# PiezoAmpHVDC.net
KiCad netlist of a schematic drawn in EAGLE
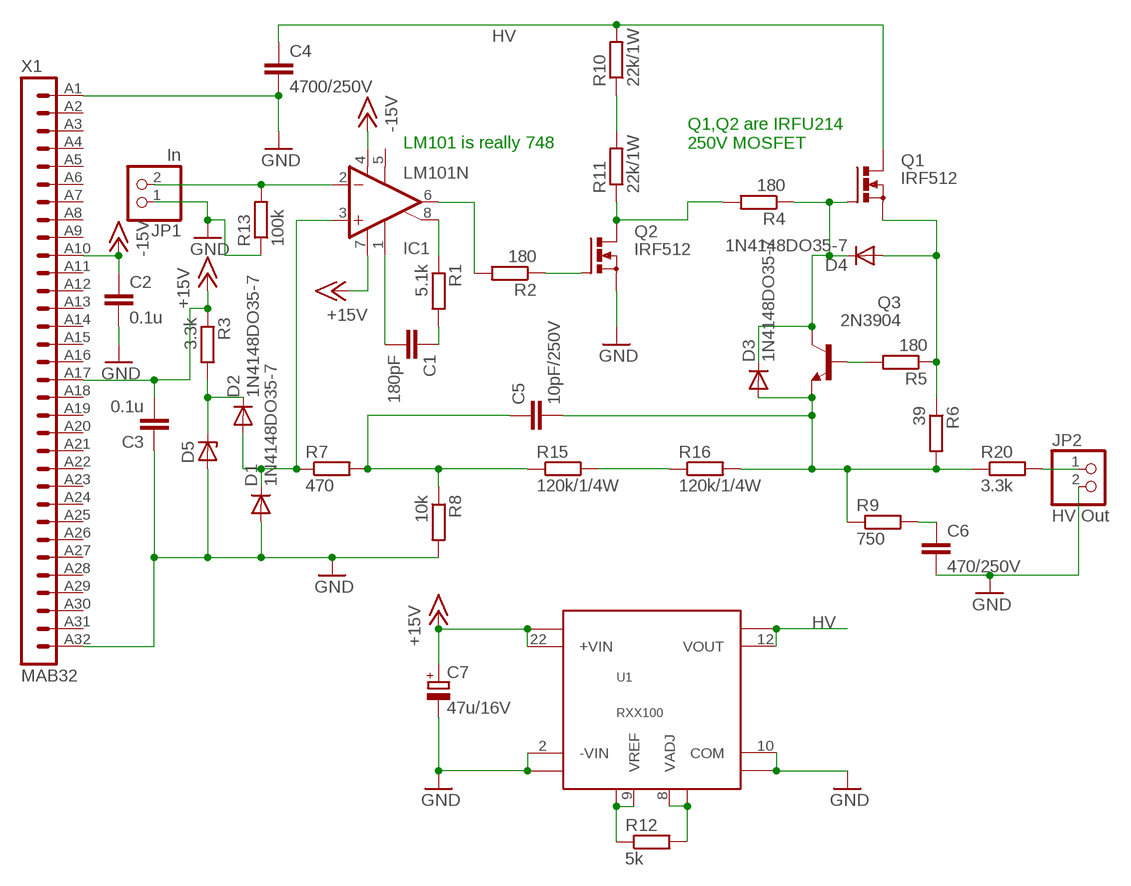
[diagram p0: schematic, sheet 1]

(export (version "E")
  (design (tool "Eeschema 10.0.6"))
  (components
    (comp (ref "C1")
      (value "180pF")
      (footprint "eagle-import:C050-030X075")
      (libsource (lib "eagle-import") (part "C-EU050-030X075"))
    )
    (comp (ref "C2")
      (value "0.1u")
      (footprint "eagle-import:C050-030X075")
      (libsource (lib "eagle-import") (part "C-EU050-030X075"))
    )
    (comp (ref "C3")
      (value "0.1u")
      (footprint "eagle-import:C050-030X075")
      (libsource (lib "eagle-import") (part "C-EU050-030X075"))
    )
    (comp (ref "C4")
      (value "4700/250V")
      (footprint "eagle-import:C075-032X103")
      (libsource (lib "eagle-import") (part "C-EU075-032X103"))
    )
    (comp (ref "C5")
      (value "10pF/250V")
      (footprint "eagle-import:C075-032X103")
      (libsource (lib "eagle-import") (part "C-EU075-032X103"))
    )
    (comp (ref "C6")
      (value "470/250V")
      (footprint "eagle-import:C075-032X103")
      (libsource (lib "eagle-import") (part "C-EU075-032X103"))
    )
    (comp (ref "C7")
      (value "47u/16V")
      (footprint "eagle-import:SANYO-OSCON_F8")
      (libsource (lib "eagle-import") (part "CPOL-EUSANYO_F8"))
    )
    (comp (ref "D1")
      (value "1N4148DO35-7")
      (footprint "eagle-import:DO35-7")
      (libsource (lib "eagle-import") (part "1N4148DO35-7"))
    )
    (comp (ref "D2")
      (value "1N4148DO35-7")
      (footprint "eagle-import:DO35-7")
      (libsource (lib "eagle-import") (part "1N4148DO35-7"))
    )
    (comp (ref "D3")
      (value "1N4148DO35-7")
      (footprint "eagle-import:DO35-7")
      (libsource (lib "eagle-import") (part "1N4148DO35-7"))
    )
    (comp (ref "D4")
      (value "1N4148DO35-7")
      (footprint "eagle-import:DO35-7")
      (libsource (lib "eagle-import") (part "1N4148DO35-7"))
    )
    (comp (ref "D5")
      (value "ZENER-DIODEDO34-7")
      (footprint "eagle-import:DO34Z7")
      (libsource (lib "eagle-import") (part "ZENER-DIODEDO34-7"))
    )
    (comp (ref "IC1")
      (value "LM101N")
      (footprint "eagle-import:DIL08")
      (libsource (lib "eagle-import") (part "LM101N"))
    )
    (comp (ref "JP1")
      (value "In")
      (footprint "eagle-import:1X02")
      (libsource (lib "eagle-import") (part "PINHD-1X2"))
    )
    (comp (ref "JP2")
      (value "HV Out")
      (footprint "eagle-import:1X02")
      (libsource (lib "eagle-import") (part "PINHD-1X2"))
    )
    (comp (ref "Q1")
      (value "IRF512")
      (footprint "eagle-import:TO220BV")
      (libsource (lib "eagle-import") (part "IRF512"))
    )
    (comp (ref "Q2")
      (value "IRF512")
      (footprint "eagle-import:TO220BV")
      (libsource (lib "eagle-import") (part "IRF512"))
    )
    (comp (ref "Q3")
      (value "2N3904")
      (footprint "eagle-import:TO92")
      (libsource (lib "eagle-import") (part "2N3904"))
    )
    (comp (ref "R1")
      (value "5.1k")
      (footprint "eagle-import:0204_7")
      (libsource (lib "eagle-import") (part "R-EU_0204/7"))
    )
    (comp (ref "R2")
      (value "180")
      (footprint "eagle-import:0204_7")
      (libsource (lib "eagle-import") (part "R-EU_0204/7"))
    )
    (comp (ref "R3")
      (value "3.3k")
      (footprint "eagle-import:0204_7")
      (libsource (lib "eagle-import") (part "R-EU_0204/7"))
    )
    (comp (ref "R4")
      (value "180")
      (footprint "eagle-import:0204_7")
      (libsource (lib "eagle-import") (part "R-EU_0204/7"))
    )
    (comp (ref "R5")
      (value "180")
      (footprint "eagle-import:0204_7")
      (libsource (lib "eagle-import") (part "R-EU_0204/7"))
    )
    (comp (ref "R6")
      (value "39")
      (footprint "eagle-import:0204_7")
      (libsource (lib "eagle-import") (part "R-EU_0204/7"))
    )
    (comp (ref "R7")
      (value "470")
      (footprint "eagle-import:0204_7")
      (libsource (lib "eagle-import") (part "R-EU_0204/7"))
    )
    (comp (ref "R8")
      (value "10k")
      (footprint "eagle-import:0204_7")
      (libsource (lib "eagle-import") (part "R-EU_0204/7"))
    )
    (comp (ref "R9")
      (value "750")
      (footprint "eagle-import:0204_7")
      (libsource (lib "eagle-import") (part "R-EU_0204/7"))
    )
    (comp (ref "R10")
      (value "22k/1W")
      (footprint "eagle-import:0411_15")
      (libsource (lib "eagle-import") (part "R-EU_0411/15"))
    )
    (comp (ref "R11")
      (value "22k/1W")
      (footprint "eagle-import:0411_15")
      (libsource (lib "eagle-import") (part "R-EU_0411/15"))
    )
    (comp (ref "R12")
      (value "5k")
      (footprint "eagle-import:0204_7")
      (libsource (lib "eagle-import") (part "R-EU_0204/7"))
    )
    (comp (ref "R13")
      (value "100k")
      (footprint "eagle-import:0204_5")
      (libsource (lib "eagle-import") (part "R-EU_0204/5"))
    )
    (comp (ref "R15")
      (value "120k/1/4W")
      (footprint "eagle-import:0411_15")
      (libsource (lib "eagle-import") (part "R-EU_0411/15"))
    )
    (comp (ref "R16")
      (value "120k/1/4W")
      (footprint "eagle-import:0411_15")
      (libsource (lib "eagle-import") (part "R-EU_0411/15"))
    )
    (comp (ref "R20")
      (value "3.3k")
      (footprint "eagle-import:0204_7")
      (libsource (lib "eagle-import") (part "R-EU_0204/7"))
    )
    (comp (ref "U1")
      (value "RXX100")
      (footprint "eagle-import:RXXDIP")
      (libsource (lib "eagle-import") (part "RXX100"))
    )
    (comp (ref "X1")
      (value "MAB32")
      (footprint "eagle-import:MAB32")
      (libsource (lib "eagle-import") (part "MAB32"))
    )
  )
  (nets
    (net (code "1") (name "+15V") (class "Default")
      (node (ref "C3") (pin "2") (pinfunction "2_2") (pintype "passive"))
      (node (ref "C7") (pin "+") (pinfunction "+_+") (pintype "passive"))
      (node (ref "IC1") (pin "7") (pinfunction "V+_7") (pintype "power_in"))
      (node (ref "R3") (pin "1") (pinfunction "1_1") (pintype "passive"))
      (node (ref "U1") (pin "22") (pinfunction "+VIN_22") (pintype "power_in"))
      (node (ref "U1") (pin "23") (pinfunction "VIN2+_23") (pintype "power_in"))
      (node (ref "X1") (pin "A17") (pinfunction "17_A17") (pintype "passive"))
    )
    (net (code "2") (name "-15V") (class "Default")
      (node (ref "C2") (pin "1") (pinfunction "1_1") (pintype "passive"))
      (node (ref "IC1") (pin "4") (pinfunction "V-_4") (pintype "power_in"))
      (node (ref "X1") (pin "A10") (pinfunction "10_A10") (pintype "passive"))
    )
    (net (code "3") (name "/HV") (class "Default")
      (node (ref "C4") (pin "1") (pinfunction "1_1") (pintype "passive"))
      (node (ref "Q1") (pin "D") (pinfunction "D_D") (pintype "passive"))
      (node (ref "R10") (pin "2") (pinfunction "2_2") (pintype "passive"))
      (node (ref "U1") (pin "12") (pinfunction "VOUT_12") (pintype "power_in"))
      (node (ref "U1") (pin "13") (pinfunction "VOUT2_13") (pintype "power_in"))
    )
    (net (code "4") (name "GND") (class "Default")
      (node (ref "C2") (pin "2") (pinfunction "2_2") (pintype "passive"))
      (node (ref "C3") (pin "1") (pinfunction "1_1") (pintype "passive"))
      (node (ref "C4") (pin "2") (pinfunction "2_2") (pintype "passive"))
      (node (ref "C6") (pin "2") (pinfunction "2_2") (pintype "passive"))
      (node (ref "C7") (pin "-") (pinfunction "-_-") (pintype "passive"))
      (node (ref "D1") (pin "A") (pinfunction "A_A") (pintype "passive"))
      (node (ref "D5") (pin "A") (pinfunction "A_A") (pintype "passive"))
      (node (ref "JP1") (pin "1") (pinfunction "1_1") (pintype "passive"))
      (node (ref "JP2") (pin "2") (pinfunction "2_2") (pintype "passive"))
      (node (ref "Q2") (pin "S") (pinfunction "S_S") (pintype "passive"))
      (node (ref "R13") (pin "1") (pinfunction "1_1") (pintype "passive"))
      (node (ref "R8") (pin "2") (pinfunction "2_2") (pintype "passive"))
      (node (ref "U1") (pin "10") (pinfunction "COM_10") (pintype "power_in"))
      (node (ref "U1") (pin "15") (pinfunction "COM2_15") (pintype "power_in"))
      (node (ref "U1") (pin "2") (pinfunction "-VIN_2") (pintype "power_in"))
      (node (ref "U1") (pin "3") (pinfunction "VIN2-_3") (pintype "power_in"))
      (node (ref "X1") (pin "A1") (pinfunction "1_A1") (pintype "passive"))
      (node (ref "X1") (pin "A32") (pinfunction "32_A32") (pintype "passive"))
    )
    (net (code "5") (name "Net-(C1-Pad1)") (class "Default")
      (node (ref "C1") (pin "1") (pinfunction "1_1") (pintype "passive"))
      (node (ref "R1") (pin "2") (pinfunction "2_2") (pintype "passive"))
    )
    (net (code "6") (name "Net-(C5-Pad1)") (class "Default")
      (node (ref "C5") (pin "1") (pinfunction "1_1") (pintype "passive"))
      (node (ref "R15") (pin "1") (pinfunction "1_1") (pintype "passive"))
      (node (ref "R7") (pin "2") (pinfunction "2_2") (pintype "passive"))
      (node (ref "R8") (pin "1") (pinfunction "1_1") (pintype "passive"))
    )
    (net (code "7") (name "Net-(C6-Pad1)") (class "Default")
      (node (ref "C6") (pin "1") (pinfunction "1_1") (pintype "passive"))
      (node (ref "R9") (pin "2") (pinfunction "2_2") (pintype "passive"))
    )
    (net (code "8") (name "Net-(D2-PadC)") (class "Default")
      (node (ref "D2") (pin "C") (pinfunction "C_C") (pintype "passive"))
      (node (ref "D5") (pin "C") (pinfunction "C_C") (pintype "passive"))
      (node (ref "R3") (pin "2") (pinfunction "2_2") (pintype "passive"))
    )
    (net (code "9") (name "Net-(D4-PadA)") (class "Default")
      (node (ref "D4") (pin "A") (pinfunction "A_A") (pintype "passive"))
      (node (ref "Q1") (pin "S") (pinfunction "S_S") (pintype "passive"))
      (node (ref "R5") (pin "1") (pinfunction "1_1") (pintype "passive"))
      (node (ref "R6") (pin "1") (pinfunction "1_1") (pintype "passive"))
    )
    (net (code "10") (name "Net-(IC1-+IN)") (class "Default")
      (node (ref "D1") (pin "C") (pinfunction "C_C") (pintype "passive"))
      (node (ref "D2") (pin "A") (pinfunction "A_A") (pintype "passive"))
      (node (ref "IC1") (pin "3") (pinfunction "+IN_3") (pintype "input"))
      (node (ref "R7") (pin "1") (pinfunction "1_1") (pintype "passive"))
    )
    (net (code "11") (name "Net-(IC1--IN)") (class "Default")
      (node (ref "IC1") (pin "2") (pinfunction "-IN_2") (pintype "input"))
      (node (ref "JP1") (pin "2") (pinfunction "2_2") (pintype "passive"))
      (node (ref "R13") (pin "2") (pinfunction "2_2") (pintype "passive"))
    )
    (net (code "12") (name "Net-(IC1-ON1)") (class "Default")
      (node (ref "C1") (pin "2") (pinfunction "2_2") (pintype "passive"))
      (node (ref "IC1") (pin "1") (pinfunction "ON1_1") (pintype "passive"))
    )
    (net (code "13") (name "Net-(IC1-ON2)") (class "Default")
      (node (ref "IC1") (pin "8") (pinfunction "ON2_8") (pintype "passive"))
      (node (ref "R1") (pin "1") (pinfunction "1_1") (pintype "passive"))
    )
    (net (code "14") (name "Net-(IC1-OUT)") (class "Default")
      (node (ref "IC1") (pin "6") (pinfunction "OUT_6") (pintype "output"))
      (node (ref "R2") (pin "2") (pinfunction "2_2") (pintype "passive"))
    )
    (net (code "15") (name "Net-(JP2-Pad1)") (class "Default")
      (node (ref "JP2") (pin "1") (pinfunction "1_1") (pintype "passive"))
      (node (ref "R20") (pin "2") (pinfunction "2_2") (pintype "passive"))
    )
    (net (code "16") (name "Net-(Q2-PadD)") (class "Default")
      (node (ref "Q2") (pin "D") (pinfunction "D_D") (pintype "passive"))
      (node (ref "R11") (pin "1") (pinfunction "1_1") (pintype "passive"))
      (node (ref "R4") (pin "2") (pinfunction "2_2") (pintype "passive"))
    )
    (net (code "17") (name "Net-(Q2-PadG)") (class "Default")
      (node (ref "Q2") (pin "G") (pinfunction "G_G") (pintype "passive"))
      (node (ref "R2") (pin "1") (pinfunction "1_1") (pintype "passive"))
    )
    (net (code "18") (name "Net-(Q3-B)") (class "Default")
      (node (ref "Q3") (pin "2") (pinfunction "B_2") (pintype "passive"))
      (node (ref "R5") (pin "2") (pinfunction "2_2") (pintype "passive"))
    )
    (net (code "19") (name "Net-(Q3-C)") (class "Default")
      (node (ref "D3") (pin "C") (pinfunction "C_C") (pintype "passive"))
      (node (ref "D4") (pin "C") (pinfunction "C_C") (pintype "passive"))
      (node (ref "Q1") (pin "G") (pinfunction "G_G") (pintype "passive"))
      (node (ref "Q3") (pin "1") (pinfunction "C_1") (pintype "passive"))
      (node (ref "R4") (pin "1") (pinfunction "1_1") (pintype "passive"))
    )
    (net (code "20") (name "Net-(Q3-E)") (class "Default")
      (node (ref "C5") (pin "2") (pinfunction "2_2") (pintype "passive"))
      (node (ref "D3") (pin "A") (pinfunction "A_A") (pintype "passive"))
      (node (ref "Q3") (pin "3") (pinfunction "E_3") (pintype "passive"))
      (node (ref "R16") (pin "2") (pinfunction "2_2") (pintype "passive"))
      (node (ref "R20") (pin "1") (pinfunction "1_1") (pintype "passive"))
      (node (ref "R6") (pin "2") (pinfunction "2_2") (pintype "passive"))
      (node (ref "R9") (pin "1") (pinfunction "1_1") (pintype "passive"))
    )
    (net (code "21") (name "Net-(R10-Pad1)") (class "Default")
      (node (ref "R10") (pin "1") (pinfunction "1_1") (pintype "passive"))
      (node (ref "R11") (pin "2") (pinfunction "2_2") (pintype "passive"))
    )
    (net (code "22") (name "Net-(R15-Pad2)") (class "Default")
      (node (ref "R15") (pin "2") (pinfunction "2_2") (pintype "passive"))
      (node (ref "R16") (pin "1") (pinfunction "1_1") (pintype "passive"))
    )
    (net (code "23") (name "Net-(U1-VADJ)") (class "Default")
      (node (ref "R12") (pin "2") (pinfunction "2_2") (pintype "passive"))
      (node (ref "U1") (pin "17") (pinfunction "VADJ2_17") (pintype "input"))
      (node (ref "U1") (pin "8") (pinfunction "VADJ_8") (pintype "input"))
    )
    (net (code "24") (name "Net-(U1-VREF)") (class "Default")
      (node (ref "R12") (pin "1") (pinfunction "1_1") (pintype "passive"))
      (node (ref "U1") (pin "16") (pinfunction "VREF2_16") (pintype "output"))
      (node (ref "U1") (pin "9") (pinfunction "VREF_9") (pintype "output"))
    )
    (net (code "25") (name "unconnected-(IC1-OPT-Pad5)") (class "Default")
      (node (ref "IC1") (pin "5") (pinfunction "OPT_5") (pintype "passive"))
    )
    (net (code "26") (name "unconnected-(X1-2-PadA2)") (class "Default")
      (node (ref "X1") (pin "A2") (pinfunction "2_A2") (pintype "passive"))
    )
    (net (code "27") (name "unconnected-(X1-3-PadA3)") (class "Default")
      (node (ref "X1") (pin "A3") (pinfunction "3_A3") (pintype "passive"))
    )
    (net (code "28") (name "unconnected-(X1-4-PadA4)") (class "Default")
      (node (ref "X1") (pin "A4") (pinfunction "4_A4") (pintype "passive"))
    )
    (net (code "29") (name "unconnected-(X1-5-PadA5)") (class "Default")
      (node (ref "X1") (pin "A5") (pinfunction "5_A5") (pintype "passive"))
    )
    (net (code "30") (name "unconnected-(X1-6-PadA6)") (class "Default")
      (node (ref "X1") (pin "A6") (pinfunction "6_A6") (pintype "passive"))
    )
    (net (code "31") (name "unconnected-(X1-7-PadA7)") (class "Default")
      (node (ref "X1") (pin "A7") (pinfunction "7_A7") (pintype "passive"))
    )
    (net (code "32") (name "unconnected-(X1-8-PadA8)") (class "Default")
      (node (ref "X1") (pin "A8") (pinfunction "8_A8") (pintype "passive"))
    )
    (net (code "33") (name "unconnected-(X1-9-PadA9)") (class "Default")
      (node (ref "X1") (pin "A9") (pinfunction "9_A9") (pintype "passive"))
    )
    (net (code "34") (name "unconnected-(X1-11-PadA11)") (class "Default")
      (node (ref "X1") (pin "A11") (pinfunction "11_A11") (pintype "passive"))
    )
    (net (code "35") (name "unconnected-(X1-12-PadA12)") (class "Default")
      (node (ref "X1") (pin "A12") (pinfunction "12_A12") (pintype "passive"))
    )
    (net (code "36") (name "unconnected-(X1-13-PadA13)") (class "Default")
      (node (ref "X1") (pin "A13") (pinfunction "13_A13") (pintype "passive"))
    )
    (net (code "37") (name "unconnected-(X1-14-PadA14)") (class "Default")
      (node (ref "X1") (pin "A14") (pinfunction "14_A14") (pintype "passive"))
    )
    (net (code "38") (name "unconnected-(X1-15-PadA15)") (class "Default")
      (node (ref "X1") (pin "A15") (pinfunction "15_A15") (pintype "passive"))
    )
    (net (code "39") (name "unconnected-(X1-16-PadA16)") (class "Default")
      (node (ref "X1") (pin "A16") (pinfunction "16_A16") (pintype "passive"))
    )
    (net (code "40") (name "unconnected-(X1-18-PadA18)") (class "Default")
      (node (ref "X1") (pin "A18") (pinfunction "18_A18") (pintype "passive"))
    )
    (net (code "41") (name "unconnected-(X1-19-PadA19)") (class "Default")
      (node (ref "X1") (pin "A19") (pinfunction "19_A19") (pintype "passive"))
    )
    (net (code "42") (name "unconnected-(X1-20-PadA20)") (class "Default")
      (node (ref "X1") (pin "A20") (pinfunction "20_A20") (pintype "passive"))
    )
    (net (code "43") (name "unconnected-(X1-21-PadA21)") (class "Default")
      (node (ref "X1") (pin "A21") (pinfunction "21_A21") (pintype "passive"))
    )
    (net (code "44") (name "unconnected-(X1-22-PadA22)") (class "Default")
      (node (ref "X1") (pin "A22") (pinfunction "22_A22") (pintype "passive"))
    )
    (net (code "45") (name "unconnected-(X1-23-PadA23)") (class "Default")
      (node (ref "X1") (pin "A23") (pinfunction "23_A23") (pintype "passive"))
    )
    (net (code "46") (name "unconnected-(X1-24-PadA24)") (class "Default")
      (node (ref "X1") (pin "A24") (pinfunction "24_A24") (pintype "passive"))
    )
    (net (code "47") (name "unconnected-(X1-25-PadA25)") (class "Default")
      (node (ref "X1") (pin "A25") (pinfunction "25_A25") (pintype "passive"))
    )
    (net (code "48") (name "unconnected-(X1-26-PadA26)") (class "Default")
      (node (ref "X1") (pin "A26") (pinfunction "26_A26") (pintype "passive"))
    )
    (net (code "49") (name "unconnected-(X1-27-PadA27)") (class "Default")
      (node (ref "X1") (pin "A27") (pinfunction "27_A27") (pintype "passive"))
    )
    (net (code "50") (name "unconnected-(X1-28-PadA28)") (class "Default")
      (node (ref "X1") (pin "A28") (pinfunction "28_A28") (pintype "passive"))
    )
    (net (code "51") (name "unconnected-(X1-29-PadA29)") (class "Default")
      (node (ref "X1") (pin "A29") (pinfunction "29_A29") (pintype "passive"))
    )
    (net (code "52") (name "unconnected-(X1-30-PadA30)") (class "Default")
      (node (ref "X1") (pin "A30") (pinfunction "30_A30") (pintype "passive"))
    )
    (net (code "53") (name "unconnected-(X1-31-PadA31)") (class "Default")
      (node (ref "X1") (pin "A31") (pinfunction "31_A31") (pintype "passive"))
    )
  )
)
